# ECG_AFE.net
KiCad netlist of a schematic drawn in EAGLE
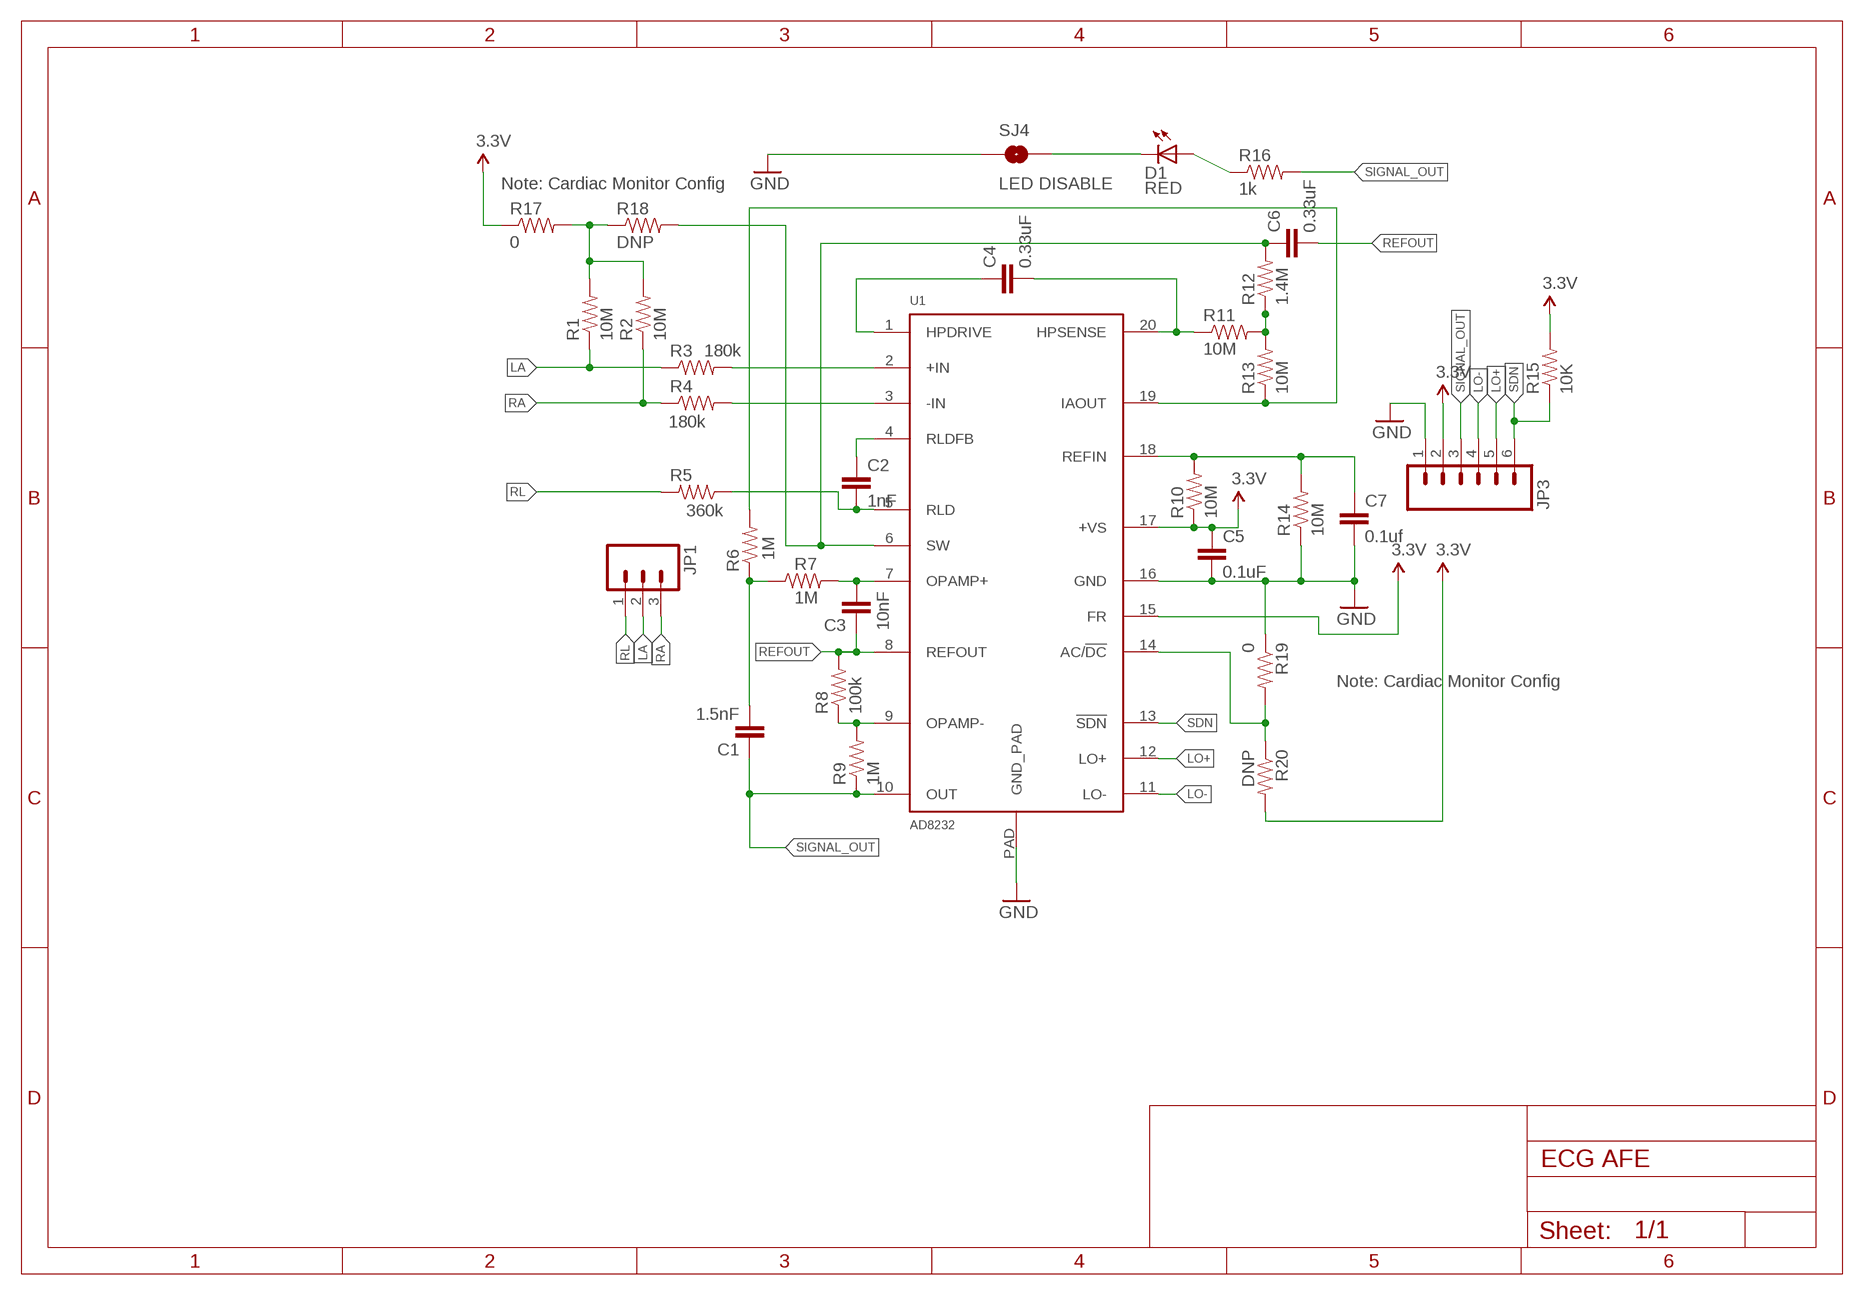
[diagram p0: schematic, sheet 1]

(export (version "E")
  (design (tool "Eeschema 10.0.6"))
  (components
    (comp (ref "C1")
      (value "1.5nF")
      (footprint "eagle-import:0603-CAP")
      (libsource (lib "eagle-import") (part "CAP0603-CAP"))
    )
    (comp (ref "C2")
      (value "1nF")
      (footprint "eagle-import:0603-CAP")
      (libsource (lib "eagle-import") (part "CAP0603-CAP"))
    )
    (comp (ref "C3")
      (value "10nF")
      (footprint "eagle-import:0603-CAP")
      (libsource (lib "eagle-import") (part "CAP0603-CAP"))
    )
    (comp (ref "C4")
      (value "0.33uF")
      (footprint "eagle-import:0805")
      (libsource (lib "eagle-import") (part "CAP0805"))
    )
    (comp (ref "C5")
      (value "0.1uF")
      (footprint "eagle-import:0603-CAP")
      (libsource (lib "eagle-import") (part "CAP0603-CAP"))
    )
    (comp (ref "C6")
      (value "0.33uF")
      (footprint "eagle-import:0805")
      (libsource (lib "eagle-import") (part "CAP0805"))
    )
    (comp (ref "C7")
      (value "0.1uf")
      (footprint "eagle-import:0603-CAP")
      (libsource (lib "eagle-import") (part "CAP0603-CAP"))
    )
    (comp (ref "D1")
      (value "RED")
      (footprint "eagle-import:LED-0603")
      (libsource (lib "eagle-import") (part "LED-RED0603"))
    )
    (comp (ref "JP1")
      (value "M03PTH")
      (footprint "eagle-import:1X03")
      (libsource (lib "eagle-import") (part "M03PTH"))
    )
    (comp (ref "JP3")
      (value "M06SIP")
      (footprint "eagle-import:1X06")
      (libsource (lib "eagle-import") (part "M06SIP"))
    )
    (comp (ref "R1")
      (value "10M")
      (footprint "eagle-import:0603-RES")
      (libsource (lib "eagle-import") (part "RESISTOR0603-RES"))
    )
    (comp (ref "R2")
      (value "10M")
      (footprint "eagle-import:0603-RES")
      (libsource (lib "eagle-import") (part "RESISTOR0603-RES"))
    )
    (comp (ref "R3")
      (value "180k")
      (footprint "eagle-import:0603-RES")
      (libsource (lib "eagle-import") (part "RESISTOR0603-RES"))
    )
    (comp (ref "R4")
      (value "180k")
      (footprint "eagle-import:0603-RES")
      (libsource (lib "eagle-import") (part "RESISTOR0603-RES"))
    )
    (comp (ref "R5")
      (value "360k")
      (footprint "eagle-import:0603-RES")
      (libsource (lib "eagle-import") (part "RESISTOR0603-RES"))
    )
    (comp (ref "R6")
      (value "1M")
      (footprint "eagle-import:0603-RES")
      (libsource (lib "eagle-import") (part "RESISTOR0603-RES"))
    )
    (comp (ref "R7")
      (value "1M")
      (footprint "eagle-import:0603-RES")
      (libsource (lib "eagle-import") (part "RESISTOR0603-RES"))
    )
    (comp (ref "R8")
      (value "100k")
      (footprint "eagle-import:0603-RES")
      (libsource (lib "eagle-import") (part "RESISTOR0603-RES"))
    )
    (comp (ref "R9")
      (value "1M")
      (footprint "eagle-import:0603-RES")
      (libsource (lib "eagle-import") (part "RESISTOR0603-RES"))
    )
    (comp (ref "R10")
      (value "10M")
      (footprint "eagle-import:0603-RES")
      (libsource (lib "eagle-import") (part "RESISTOR0603-RES"))
    )
    (comp (ref "R11")
      (value "10M")
      (footprint "eagle-import:0603-RES")
      (libsource (lib "eagle-import") (part "RESISTOR0603-RES"))
    )
    (comp (ref "R12")
      (value "1.4M")
      (footprint "eagle-import:0603-RES")
      (libsource (lib "eagle-import") (part "RESISTOR0603-RES"))
    )
    (comp (ref "R13")
      (value "10M")
      (footprint "eagle-import:0603-RES")
      (libsource (lib "eagle-import") (part "RESISTOR0603-RES"))
    )
    (comp (ref "R14")
      (value "10M")
      (footprint "eagle-import:0603-RES")
      (libsource (lib "eagle-import") (part "RESISTOR0603-RES"))
    )
    (comp (ref "R15")
      (value "10K")
      (footprint "eagle-import:0603-RES")
      (libsource (lib "eagle-import") (part "10KOHM1/10W1%(0603)0603"))
    )
    (comp (ref "R16")
      (value "1k")
      (footprint "eagle-import:0603-RES")
      (libsource (lib "eagle-import") (part "1K-1%"))
    )
    (comp (ref "R17")
      (value "0")
      (footprint "eagle-import:0603")
      (libsource (lib "eagle-import") (part "0OHM1/10W5%(0603)"))
    )
    (comp (ref "R18")
      (value "DNP")
      (footprint "eagle-import:0603")
      (libsource (lib "eagle-import") (part "0OHM1/10W5%(0603)"))
    )
    (comp (ref "R19")
      (value "0")
      (footprint "eagle-import:0603")
      (libsource (lib "eagle-import") (part "0OHM1/10W5%(0603)"))
    )
    (comp (ref "R20")
      (value "DNP")
      (footprint "eagle-import:0603")
      (libsource (lib "eagle-import") (part "0OHM1/10W5%(0603)"))
    )
    (comp (ref "SJ4")
      (value "LED DISABLE")
      (footprint "eagle-import:SJ_2S-TRACE")
      (libsource (lib "eagle-import") (part "SOLDERJUMPERTRACE"))
    )
    (comp (ref "U1")
      (value "AD8232")
      (footprint "eagle-import:LFCSP_20")
      (libsource (lib "eagle-import") (part "AD8232"))
    )
  )
  (nets
    (net (code "1") (name "3.3V") (class "Default")
      (node (ref "C5") (pin "1") (pinfunction "1_1") (pintype "passive"))
      (node (ref "JP3") (pin "2") (pinfunction "2_2") (pintype "passive"))
      (node (ref "R10") (pin "1") (pinfunction "1_1") (pintype "passive"))
      (node (ref "R15") (pin "2") (pinfunction "2_2") (pintype "passive"))
      (node (ref "R17") (pin "1") (pinfunction "1_1") (pintype "passive"))
      (node (ref "R20") (pin "2") (pinfunction "2_2") (pintype "passive"))
      (node (ref "U1") (pin "15") (pinfunction "FR_15") (pintype "bidirectional"))
      (node (ref "U1") (pin "17") (pinfunction "+VS_17") (pintype "bidirectional"))
    )
    (net (code "2") (name "GND") (class "Default")
      (node (ref "C5") (pin "2") (pinfunction "2_2") (pintype "passive"))
      (node (ref "C7") (pin "2") (pinfunction "2_2") (pintype "passive"))
      (node (ref "JP3") (pin "1") (pinfunction "1_1") (pintype "passive"))
      (node (ref "R14") (pin "1") (pinfunction "1_1") (pintype "passive"))
      (node (ref "R19") (pin "1") (pinfunction "1_1") (pintype "passive"))
      (node (ref "SJ4") (pin "1") (pinfunction "1_1") (pintype "passive"))
      (node (ref "U1") (pin "16") (pinfunction "GND_16") (pintype "bidirectional"))
      (node (ref "U1") (pin "PAD") (pinfunction "GND_PAD_PAD") (pintype "bidirectional"))
    )
    (net (code "3") (name "LA") (class "Default")
      (node (ref "JP1") (pin "2") (pinfunction "2_2") (pintype "passive"))
      (node (ref "R1") (pin "1") (pinfunction "1_1") (pintype "passive"))
      (node (ref "R3") (pin "1") (pinfunction "1_1") (pintype "passive"))
    )
    (net (code "4") (name "LO+") (class "Default")
      (node (ref "JP3") (pin "5") (pinfunction "5_5") (pintype "passive"))
      (node (ref "U1") (pin "12") (pinfunction "LO+_12") (pintype "bidirectional"))
    )
    (net (code "5") (name "LO-") (class "Default")
      (node (ref "JP3") (pin "4") (pinfunction "4_4") (pintype "passive"))
      (node (ref "U1") (pin "11") (pinfunction "LO-_11") (pintype "bidirectional"))
    )
    (net (code "6") (name "Net-(C1-Pad2)") (class "Default")
      (node (ref "C1") (pin "2") (pinfunction "2_2") (pintype "passive"))
      (node (ref "R6") (pin "1") (pinfunction "1_1") (pintype "passive"))
      (node (ref "R7") (pin "1") (pinfunction "1_1") (pintype "passive"))
    )
    (net (code "7") (name "Net-(D1-PadA)") (class "Default")
      (node (ref "D1") (pin "A") (pinfunction "A_A") (pintype "passive"))
      (node (ref "R16") (pin "1") (pinfunction "1_1") (pintype "passive"))
    )
    (net (code "8") (name "Net-(D1-PadC)") (class "Default")
      (node (ref "D1") (pin "C") (pinfunction "C_C") (pintype "passive"))
      (node (ref "SJ4") (pin "2") (pinfunction "2_2") (pintype "passive"))
    )
    (net (code "9") (name "Net-(R1-Pad2)") (class "Default")
      (node (ref "R1") (pin "2") (pinfunction "2_2") (pintype "passive"))
      (node (ref "R17") (pin "2") (pinfunction "2_2") (pintype "passive"))
      (node (ref "R18") (pin "1") (pinfunction "1_1") (pintype "passive"))
      (node (ref "R2") (pin "2") (pinfunction "2_2") (pintype "passive"))
    )
    (net (code "10") (name "Net-(R11-Pad2)") (class "Default")
      (node (ref "R11") (pin "2") (pinfunction "2_2") (pintype "passive"))
      (node (ref "R12") (pin "1") (pinfunction "1_1") (pintype "passive"))
      (node (ref "R13") (pin "2") (pinfunction "2_2") (pintype "passive"))
    )
    (net (code "11") (name "Net-(U1-+IN)") (class "Default")
      (node (ref "R3") (pin "2") (pinfunction "2_2") (pintype "passive"))
      (node (ref "U1") (pin "2") (pinfunction "+IN_2") (pintype "bidirectional"))
    )
    (net (code "12") (name "Net-(U1--IN)") (class "Default")
      (node (ref "R4") (pin "2") (pinfunction "2_2") (pintype "passive"))
      (node (ref "U1") (pin "3") (pinfunction "-IN_3") (pintype "bidirectional"))
    )
    (net (code "13") (name "Net-(U1-AC{slash}~{DC})") (class "Default")
      (node (ref "R19") (pin "2") (pinfunction "2_2") (pintype "passive"))
      (node (ref "R20") (pin "1") (pinfunction "1_1") (pintype "passive"))
      (node (ref "U1") (pin "14") (pinfunction "AC/~{DC}_14") (pintype "bidirectional"))
    )
    (net (code "14") (name "Net-(U1-HPDRIVE)") (class "Default")
      (node (ref "C4") (pin "1") (pinfunction "1_1") (pintype "passive"))
      (node (ref "U1") (pin "1") (pinfunction "HPDRIVE_1") (pintype "bidirectional"))
    )
    (net (code "15") (name "Net-(U1-HPSENSE)") (class "Default")
      (node (ref "C4") (pin "2") (pinfunction "2_2") (pintype "passive"))
      (node (ref "R11") (pin "1") (pinfunction "1_1") (pintype "passive"))
      (node (ref "U1") (pin "20") (pinfunction "HPSENSE_20") (pintype "bidirectional"))
    )
    (net (code "16") (name "Net-(U1-IAOUT)") (class "Default")
      (node (ref "R13") (pin "1") (pinfunction "1_1") (pintype "passive"))
      (node (ref "R6") (pin "2") (pinfunction "2_2") (pintype "passive"))
      (node (ref "U1") (pin "19") (pinfunction "IAOUT_19") (pintype "bidirectional"))
    )
    (net (code "17") (name "Net-(U1-OPAMP+)") (class "Default")
      (node (ref "C3") (pin "2") (pinfunction "2_2") (pintype "passive"))
      (node (ref "R7") (pin "2") (pinfunction "2_2") (pintype "passive"))
      (node (ref "U1") (pin "7") (pinfunction "OPAMP+_7") (pintype "bidirectional"))
    )
    (net (code "18") (name "Net-(U1-OPAMP-)") (class "Default")
      (node (ref "R8") (pin "1") (pinfunction "1_1") (pintype "passive"))
      (node (ref "R9") (pin "2") (pinfunction "2_2") (pintype "passive"))
      (node (ref "U1") (pin "9") (pinfunction "OPAMP-_9") (pintype "bidirectional"))
    )
    (net (code "19") (name "Net-(U1-REFIN)") (class "Default")
      (node (ref "C7") (pin "1") (pinfunction "1_1") (pintype "passive"))
      (node (ref "R10") (pin "2") (pinfunction "2_2") (pintype "passive"))
      (node (ref "R14") (pin "2") (pinfunction "2_2") (pintype "passive"))
      (node (ref "U1") (pin "18") (pinfunction "REFIN_18") (pintype "bidirectional"))
    )
    (net (code "20") (name "Net-(U1-RLD)") (class "Default")
      (node (ref "C2") (pin "2") (pinfunction "2_2") (pintype "passive"))
      (node (ref "R5") (pin "1") (pinfunction "1_1") (pintype "passive"))
      (node (ref "U1") (pin "5") (pinfunction "RLD_5") (pintype "bidirectional"))
    )
    (net (code "21") (name "Net-(U1-RLDFB)") (class "Default")
      (node (ref "C2") (pin "1") (pinfunction "1_1") (pintype "passive"))
      (node (ref "U1") (pin "4") (pinfunction "RLDFB_4") (pintype "bidirectional"))
    )
    (net (code "22") (name "Net-(U1-SW)") (class "Default")
      (node (ref "C6") (pin "1") (pinfunction "1_1") (pintype "passive"))
      (node (ref "R12") (pin "2") (pinfunction "2_2") (pintype "passive"))
      (node (ref "R18") (pin "2") (pinfunction "2_2") (pintype "passive"))
      (node (ref "U1") (pin "6") (pinfunction "SW_6") (pintype "bidirectional"))
    )
    (net (code "23") (name "RA") (class "Default")
      (node (ref "JP1") (pin "3") (pinfunction "3_3") (pintype "passive"))
      (node (ref "R2") (pin "1") (pinfunction "1_1") (pintype "passive"))
      (node (ref "R4") (pin "1") (pinfunction "1_1") (pintype "passive"))
    )
    (net (code "24") (name "REFOUT") (class "Default")
      (node (ref "C3") (pin "1") (pinfunction "1_1") (pintype "passive"))
      (node (ref "C6") (pin "2") (pinfunction "2_2") (pintype "passive"))
      (node (ref "R8") (pin "2") (pinfunction "2_2") (pintype "passive"))
      (node (ref "U1") (pin "8") (pinfunction "REFOUT_8") (pintype "bidirectional"))
    )
    (net (code "25") (name "RL") (class "Default")
      (node (ref "JP1") (pin "1") (pinfunction "1_1") (pintype "passive"))
      (node (ref "R5") (pin "2") (pinfunction "2_2") (pintype "passive"))
    )
    (net (code "26") (name "SDN") (class "Default")
      (node (ref "JP3") (pin "6") (pinfunction "6_6") (pintype "passive"))
      (node (ref "R15") (pin "1") (pinfunction "1_1") (pintype "passive"))
      (node (ref "U1") (pin "13") (pinfunction "~{SDN}_13") (pintype "bidirectional"))
    )
    (net (code "27") (name "SIGNAL_OUT") (class "Default")
      (node (ref "C1") (pin "1") (pinfunction "1_1") (pintype "passive"))
      (node (ref "JP3") (pin "3") (pinfunction "3_3") (pintype "passive"))
      (node (ref "R16") (pin "2") (pinfunction "2_2") (pintype "passive"))
      (node (ref "R9") (pin "1") (pinfunction "1_1") (pintype "passive"))
      (node (ref "U1") (pin "10") (pinfunction "OUT_10") (pintype "bidirectional"))
    )
  )
)
